# Companion_Board.net
KiCad netlist of a schematic drawn in EAGLE
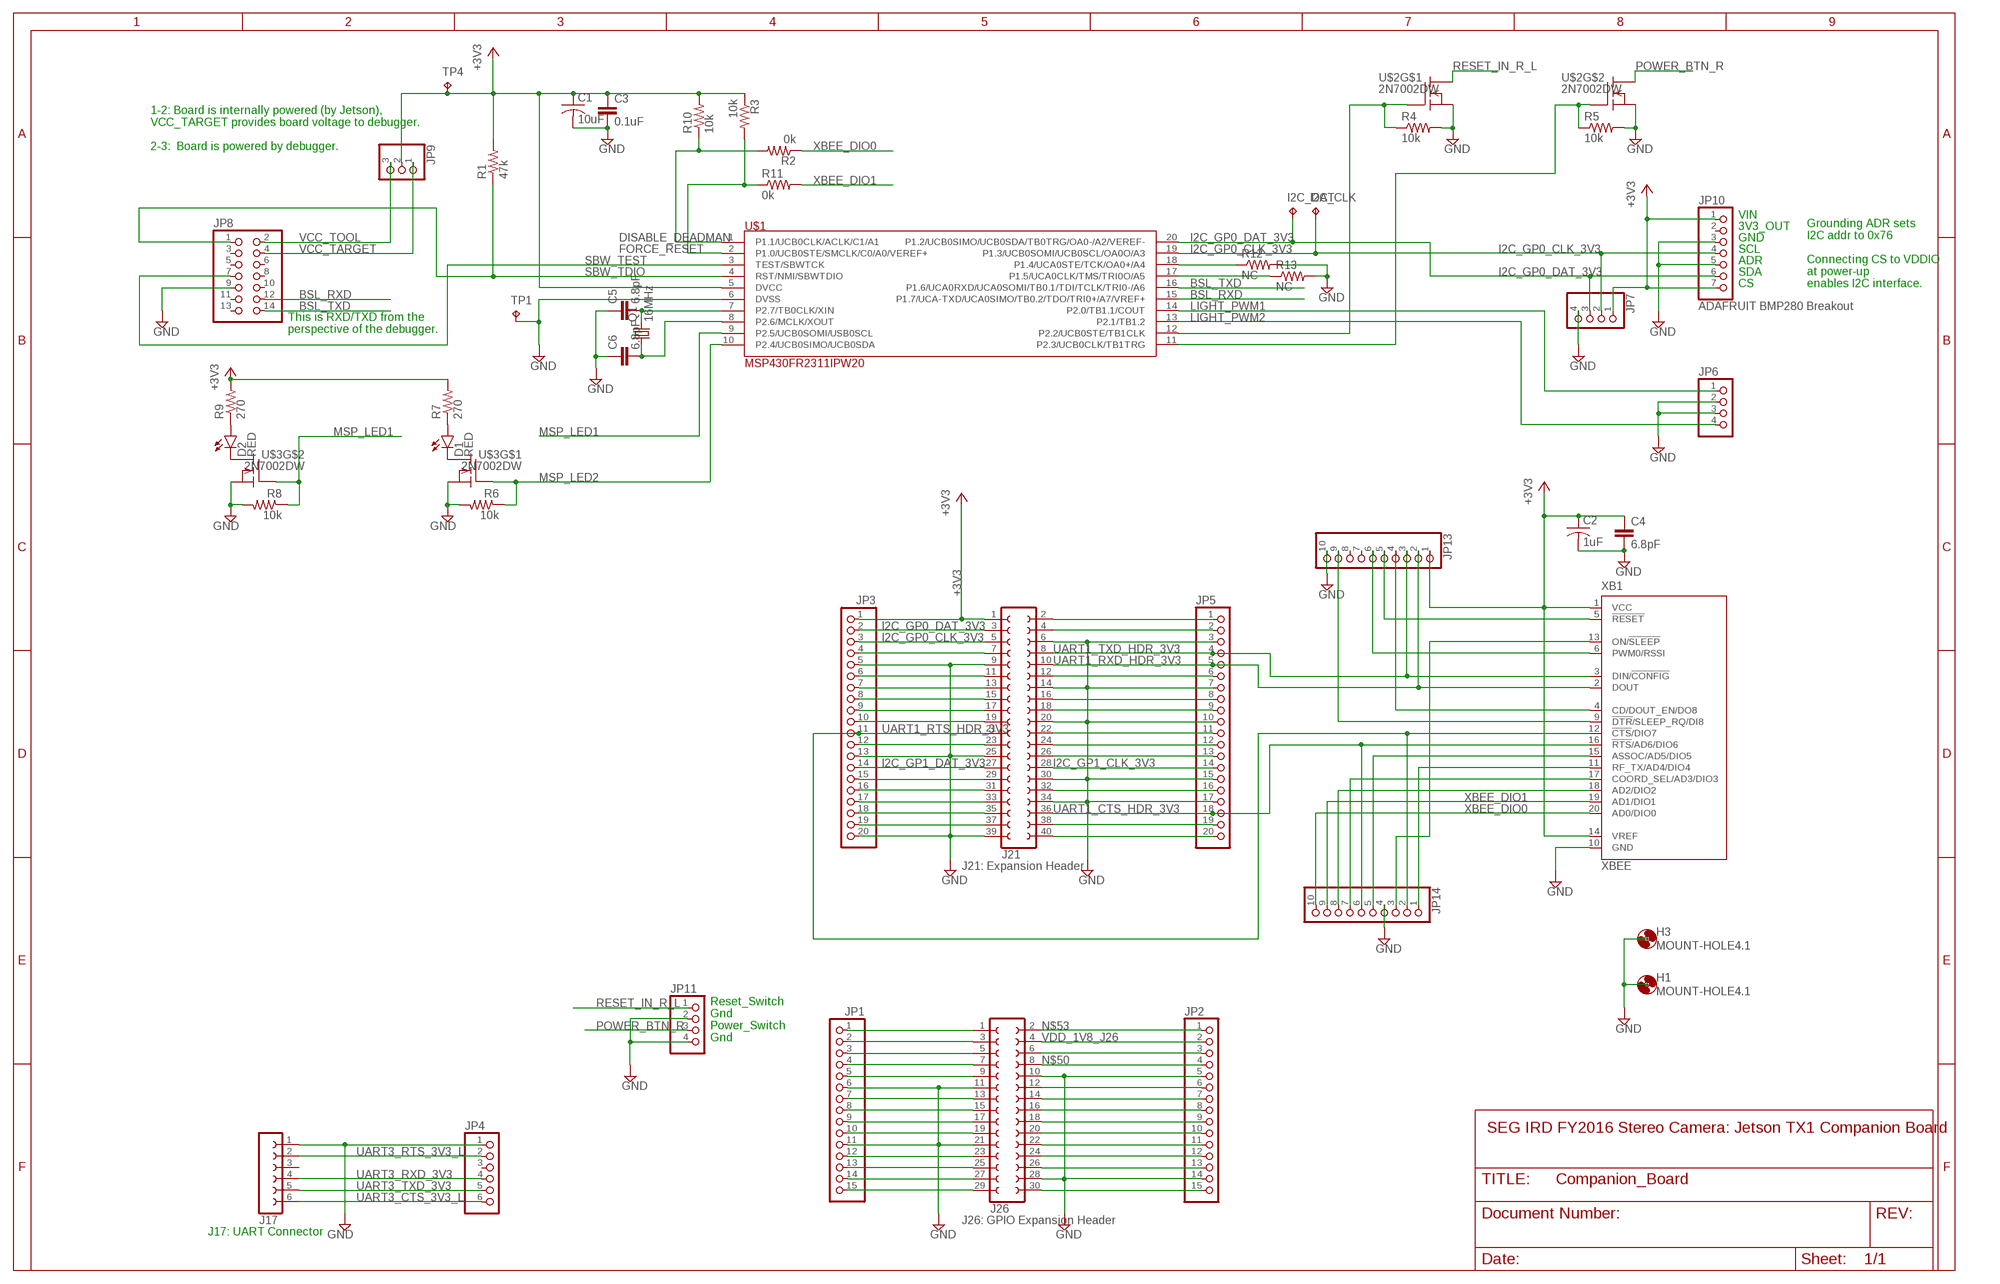
[diagram p0: schematic, sheet 1]

(export (version "E")
  (design (tool "Eeschema 10.0.6"))
  (components
    (comp (ref "C1")
      (value "10uF")
      (footprint "eagle-import:C1206")
      (libsource (lib "eagle-import") (part "C-USC1206"))
    )
    (comp (ref "C2")
      (value "1uF")
      (footprint "eagle-import:C1206")
      (libsource (lib "eagle-import") (part "C-USC1206"))
    )
    (comp (ref "C3")
      (value "0.1uF")
      (footprint "eagle-import:C0805")
      (libsource (lib "eagle-import") (part "C-EUC0805"))
    )
    (comp (ref "C4")
      (value "6.8pF")
      (footprint "eagle-import:C0805")
      (libsource (lib "eagle-import") (part "C-EUC0805"))
    )
    (comp (ref "C5")
      (value "6.8pF")
      (footprint "eagle-import:C0805")
      (libsource (lib "eagle-import") (part "C-EUC0805"))
    )
    (comp (ref "C6")
      (value "6.8pF")
      (footprint "eagle-import:C0805")
      (libsource (lib "eagle-import") (part "C-EUC0805"))
    )
    (comp (ref "D1")
      (value "RED")
      (footprint "eagle-import:LED-1206")
      (libsource (lib "eagle-import") (part "LED-RED1206"))
    )
    (comp (ref "D2")
      (value "RED")
      (footprint "eagle-import:LED-1206")
      (libsource (lib "eagle-import") (part "LED-RED1206"))
    )
    (comp (ref "H1")
      (value "MOUNT-HOLE4.1")
      (footprint "eagle-import:4,1")
      (libsource (lib "eagle-import") (part "MOUNT-HOLE4.1"))
    )
    (comp (ref "H3")
      (value "MOUNT-HOLE4.1")
      (footprint "eagle-import:4,1")
      (libsource (lib "eagle-import") (part "MOUNT-HOLE4.1"))
    )
    (comp (ref "I2C_CLK")
      (value "TPPAD1-13")
      (footprint "eagle-import:P1-13")
      (libsource (lib "eagle-import") (part "TPPAD1-13"))
    )
    (comp (ref "I2C_DAT")
      (value "TPPAD1-13")
      (footprint "eagle-import:P1-13")
      (libsource (lib "eagle-import") (part "TPPAD1-13"))
    )
    (comp (ref "J17")
      (value "FE06-1")
      (footprint "eagle-import:FE06")
      (libsource (lib "eagle-import") (part "FE06-1"))
    )
    (comp (ref "J21")
      (value "FE20-2")
      (footprint "eagle-import:FE20-2")
      (libsource (lib "eagle-import") (part "FE20-2"))
    )
    (comp (ref "J26")
      (value "FE15-2")
      (footprint "eagle-import:FE15-2")
      (libsource (lib "eagle-import") (part "FE15-2"))
    )
    (comp (ref "JP1")
      (value "PINHD-1X15")
      (footprint "eagle-import:1X15")
      (libsource (lib "eagle-import") (part "PINHD-1X15"))
    )
    (comp (ref "JP2")
      (value "PINHD-1X15")
      (footprint "eagle-import:1X15")
      (libsource (lib "eagle-import") (part "PINHD-1X15"))
    )
    (comp (ref "JP3")
      (value "PINHD-1X20")
      (footprint "eagle-import:1X20")
      (libsource (lib "eagle-import") (part "PINHD-1X20"))
    )
    (comp (ref "JP4")
      (value "PINHD-1X6")
      (footprint "eagle-import:1X06")
      (libsource (lib "eagle-import") (part "PINHD-1X6"))
    )
    (comp (ref "JP5")
      (value "PINHD-1X20")
      (footprint "eagle-import:1X20")
      (libsource (lib "eagle-import") (part "PINHD-1X20"))
    )
    (comp (ref "JP6")
      (value "PINHD-1X4/90")
      (footprint "eagle-import:1X04_90")
      (libsource (lib "eagle-import") (part "PINHD-1X4/90"))
    )
    (comp (ref "JP7")
      (value "PINHD-1X4")
      (footprint "eagle-import:1X04")
      (libsource (lib "eagle-import") (part "PINHD-1X4"))
    )
    (comp (ref "JP8")
      (value "PINHD-2X7")
      (footprint "eagle-import:2X07")
      (libsource (lib "eagle-import") (part "PINHD-2X7"))
    )
    (comp (ref "JP9")
      (value "PINHD-1X3")
      (footprint "eagle-import:1X03")
      (libsource (lib "eagle-import") (part "PINHD-1X3"))
    )
    (comp (ref "JP10")
      (value "ADAFRUIT BMP280 Breakout")
      (footprint "eagle-import:1X07")
      (libsource (lib "eagle-import") (part "ADAFRUIT_BMP280_BREAKOUT"))
    )
    (comp (ref "JP11")
      (value "PINHD-1X4/90")
      (footprint "eagle-import:1X04_90")
      (libsource (lib "eagle-import") (part "PINHD-1X4/90"))
    )
    (comp (ref "JP13")
      (value "PINHD-1X10")
      (footprint "eagle-import:1X10")
      (libsource (lib "eagle-import") (part "PINHD-1X10"))
    )
    (comp (ref "JP14")
      (value "PINHD-1X10")
      (footprint "eagle-import:1X10")
      (libsource (lib "eagle-import") (part "PINHD-1X10"))
    )
    (comp (ref "Q1")
      (value "16MHz")
      (footprint "eagle-import:HC49UP")
      (libsource (lib "eagle-import") (part "CRYSTALHC49UP"))
    )
    (comp (ref "R1")
      (value "47k")
      (footprint "eagle-import:R0805")
      (libsource (lib "eagle-import") (part "R-US_R0805"))
    )
    (comp (ref "R2")
      (value "0k")
      (footprint "eagle-import:R0805")
      (libsource (lib "eagle-import") (part "R-US_R0805"))
    )
    (comp (ref "R3")
      (value "10k")
      (footprint "eagle-import:R0805")
      (libsource (lib "eagle-import") (part "R-US_R0805"))
    )
    (comp (ref "R4")
      (value "10k")
      (footprint "eagle-import:R0805")
      (libsource (lib "eagle-import") (part "R-US_R0805"))
    )
    (comp (ref "R5")
      (value "10k")
      (footprint "eagle-import:R0805")
      (libsource (lib "eagle-import") (part "R-US_R0805"))
    )
    (comp (ref "R6")
      (value "10k")
      (footprint "eagle-import:R0805")
      (libsource (lib "eagle-import") (part "R-US_R0805"))
    )
    (comp (ref "R7")
      (value "270")
      (footprint "eagle-import:R0805")
      (libsource (lib "eagle-import") (part "R-US_R0805"))
    )
    (comp (ref "R8")
      (value "10k")
      (footprint "eagle-import:R0805")
      (libsource (lib "eagle-import") (part "R-US_R0805"))
    )
    (comp (ref "R9")
      (value "270")
      (footprint "eagle-import:R0805")
      (libsource (lib "eagle-import") (part "R-US_R0805"))
    )
    (comp (ref "R10")
      (value "10k")
      (footprint "eagle-import:R0805")
      (libsource (lib "eagle-import") (part "R-US_R0805"))
    )
    (comp (ref "R11")
      (value "0k")
      (footprint "eagle-import:R0805")
      (libsource (lib "eagle-import") (part "R-US_R0805"))
    )
    (comp (ref "R12")
      (value "NC")
      (footprint "eagle-import:R0805")
      (libsource (lib "eagle-import") (part "R-US_R0805"))
    )
    (comp (ref "R13")
      (value "NC")
      (footprint "eagle-import:R0805")
      (libsource (lib "eagle-import") (part "R-US_R0805"))
    )
    (comp (ref "TP1")
      (value "TPPAD1-13")
      (footprint "eagle-import:P1-13")
      (libsource (lib "eagle-import") (part "TPPAD1-13"))
    )
    (comp (ref "TP4")
      (value "TPPAD1-13")
      (footprint "eagle-import:P1-13")
      (libsource (lib "eagle-import") (part "TPPAD1-13"))
    )
    (comp (ref "U$1")
      (value "MSP430FR2311IPW20")
      (footprint "eagle-import:SOP65P640X120-20N")
      (libsource (lib "eagle-import") (part "MSP430FR2311IPW20"))
    )
    (comp (ref "U$2")
      (value "2N7002DW")
      (footprint "eagle-import:SOT363")
      (libsource (lib "eagle-import") (part "2N7002DW"))
    )
    (comp (ref "U$3")
      (value "2N7002DW")
      (footprint "eagle-import:SOT363")
      (libsource (lib "eagle-import") (part "2N7002DW"))
    )
    (comp (ref "XB1")
      (value "XBEE")
      (footprint "eagle-import:XBEE")
      (fields (field (name "MPN") "XBP24-Z7UIT-004"))
      (libsource (lib "eagle-import") (part "XBEE"))
    )
  )
  (nets
    (net (code "1") (name "+3V3") (class "Default")
      (node (ref "C1") (pin "1") (pinfunction "1_1") (pintype "passive"))
      (node (ref "C2") (pin "1") (pinfunction "1_1") (pintype "passive"))
      (node (ref "C3") (pin "1") (pinfunction "1_1") (pintype "passive"))
      (node (ref "C4") (pin "1") (pinfunction "1_1") (pintype "passive"))
      (node (ref "J21") (pin "1") (pinfunction "1_1") (pintype "passive"))
      (node (ref "JP10") (pin "1") (pinfunction "1_1") (pintype "passive"))
      (node (ref "JP10") (pin "7") (pinfunction "7_7") (pintype "passive"))
      (node (ref "JP13") (pin "1") (pinfunction "1_1") (pintype "passive"))
      (node (ref "JP3") (pin "1") (pinfunction "1_1") (pintype "passive"))
      (node (ref "JP7") (pin "1") (pinfunction "1_1") (pintype "passive"))
      (node (ref "JP9") (pin "2") (pinfunction "2_2") (pintype "passive"))
      (node (ref "R1") (pin "2") (pinfunction "2_2") (pintype "passive"))
      (node (ref "R10") (pin "2") (pinfunction "2_2") (pintype "passive"))
      (node (ref "R3") (pin "1") (pinfunction "1_1") (pintype "passive"))
      (node (ref "R7") (pin "2") (pinfunction "2_2") (pintype "passive"))
      (node (ref "R9") (pin "2") (pinfunction "2_2") (pintype "passive"))
      (node (ref "TP4") (pin "TP") (pinfunction "TP_TP") (pintype "input"))
      (node (ref "U$1") (pin "5") (pinfunction "DVCC_5") (pintype "bidirectional"))
      (node (ref "XB1") (pin "1") (pinfunction "VCC_1") (pintype "power_in"))
      (node (ref "XB1") (pin "14") (pinfunction "VREF_14") (pintype "input"))
    )
    (net (code "2") (name "/BSL_RXD") (class "Default")
      (node (ref "JP8") (pin "12") (pinfunction "12_12") (pintype "passive"))
      (node (ref "U$1") (pin "15") (pinfunction "P1.7/UCA-TXD/UCA0SIMO/TB0.2/TDO/TRI0+/A7/VREF+_15") (pintype "bidirectional"))
    )
    (net (code "3") (name "/BSL_TXD") (class "Default")
      (node (ref "JP8") (pin "14") (pinfunction "14_14") (pintype "passive"))
      (node (ref "U$1") (pin "16") (pinfunction "P1.6/UCA0RXD/UCA0SOMI/TB0.1/TDI/TCLK/TRI0-/A6_16") (pintype "bidirectional"))
    )
    (net (code "4") (name "/DISABLE_DEADMAN") (class "Default")
      (node (ref "R10") (pin "1") (pinfunction "1_1") (pintype "passive"))
      (node (ref "R2") (pin "2") (pinfunction "2_2") (pintype "passive"))
      (node (ref "U$1") (pin "1") (pinfunction "P1.1/UCB0CLK/ACLK/C1/A1_1") (pintype "bidirectional"))
    )
    (net (code "5") (name "/FORCE_RESET") (class "Default")
      (node (ref "R11") (pin "1") (pinfunction "1_1") (pintype "passive"))
      (node (ref "R3") (pin "2") (pinfunction "2_2") (pintype "passive"))
      (node (ref "U$1") (pin "2") (pinfunction "P1.0/UCB0STE/SMCLK/C0/A0/VEREF+_2") (pintype "bidirectional"))
    )
    (net (code "6") (name "/I2C_GP0_CLK_3V3") (class "Default")
      (node (ref "I2C_CLK") (pin "TP") (pinfunction "TP_TP") (pintype "input"))
      (node (ref "J21") (pin "5") (pinfunction "5_5") (pintype "passive"))
      (node (ref "JP10") (pin "4") (pinfunction "4_4") (pintype "passive"))
      (node (ref "JP3") (pin "3") (pinfunction "3_3") (pintype "passive"))
      (node (ref "JP7") (pin "2") (pinfunction "2_2") (pintype "passive"))
      (node (ref "U$1") (pin "19") (pinfunction "P1.3/UCB0SOMI/UCB0SCL/OA0O/A3_19") (pintype "bidirectional"))
    )
    (net (code "7") (name "/I2C_GP0_DAT_3V3") (class "Default")
      (node (ref "I2C_DAT") (pin "TP") (pinfunction "TP_TP") (pintype "input"))
      (node (ref "J21") (pin "3") (pinfunction "3_3") (pintype "passive"))
      (node (ref "JP10") (pin "6") (pinfunction "6_6") (pintype "passive"))
      (node (ref "JP3") (pin "2") (pinfunction "2_2") (pintype "passive"))
      (node (ref "JP7") (pin "3") (pinfunction "3_3") (pintype "passive"))
      (node (ref "U$1") (pin "20") (pinfunction "P1.2/UCB0SIMO/UCB0SDA/TB0TRG/OA0-/A2/VEREF-_20") (pintype "bidirectional"))
    )
    (net (code "8") (name "/I2C_GP1_CLK_3V3") (class "Default")
      (node (ref "J21") (pin "28") (pinfunction "28_28") (pintype "passive"))
      (node (ref "JP5") (pin "14") (pinfunction "14_14") (pintype "passive"))
    )
    (net (code "9") (name "/I2C_GP1_DAT_3V3") (class "Default")
      (node (ref "J21") (pin "27") (pinfunction "27_27") (pintype "passive"))
      (node (ref "JP3") (pin "14") (pinfunction "14_14") (pintype "passive"))
    )
    (net (code "10") (name "/LIGHT_PWM1") (class "Default")
      (node (ref "JP6") (pin "1") (pinfunction "1_1") (pintype "passive"))
      (node (ref "U$1") (pin "14") (pinfunction "P2.0/TB1.1/COUT_14") (pintype "bidirectional"))
    )
    (net (code "11") (name "/LIGHT_PWM2") (class "Default")
      (node (ref "JP6") (pin "4") (pinfunction "4_4") (pintype "passive"))
      (node (ref "U$1") (pin "13") (pinfunction "P2.1/TB1.2_13") (pintype "bidirectional"))
    )
    (net (code "12") (name "/MSP_LED1") (class "Default")
      (node (ref "R8") (pin "1") (pinfunction "1_1") (pintype "passive"))
      (node (ref "U$1") (pin "9") (pinfunction "P2.5/UCB0SOMI/USB0SCL_9") (pintype "bidirectional"))
      (node (ref "U$3") (pin "5") (pinfunction "G_5") (pintype "passive"))
    )
    (net (code "13") (name "/MSP_LED2") (class "Default")
      (node (ref "R6") (pin "1") (pinfunction "1_1") (pintype "passive"))
      (node (ref "U$1") (pin "10") (pinfunction "P2.4/UCB0SIMO/UCB0SDA_10") (pintype "bidirectional"))
      (node (ref "U$3") (pin "2") (pinfunction "G_2") (pintype "passive"))
    )
    (net (code "14") (name "/N$50") (class "Default")
      (node (ref "J21") (pin "4") (pinfunction "4_4") (pintype "passive"))
      (node (ref "JP5") (pin "2") (pinfunction "2_2") (pintype "passive"))
    )
    (net (code "15") (name "/N$53") (class "Default")
      (node (ref "J21") (pin "17") (pinfunction "17_17") (pintype "passive"))
      (node (ref "JP3") (pin "9") (pinfunction "9_9") (pintype "passive"))
    )
    (net (code "16") (name "/POWER_BTN_R") (class "Default")
      (node (ref "JP11") (pin "3") (pinfunction "3_3") (pintype "passive"))
      (node (ref "U$2") (pin "3") (pinfunction "D_3") (pintype "passive"))
    )
    (net (code "17") (name "/RESET_IN_R_L") (class "Default")
      (node (ref "JP11") (pin "1") (pinfunction "1_1") (pintype "passive"))
      (node (ref "U$2") (pin "6") (pinfunction "D_6") (pintype "passive"))
    )
    (net (code "18") (name "/SBW_TDIO") (class "Default")
      (node (ref "JP8") (pin "1") (pinfunction "1_1") (pintype "passive"))
      (node (ref "R1") (pin "1") (pinfunction "1_1") (pintype "passive"))
      (node (ref "U$1") (pin "4") (pinfunction "RST/NMI/SBWTDIO_4") (pintype "bidirectional"))
    )
    (net (code "19") (name "/SBW_TEST") (class "Default")
      (node (ref "JP8") (pin "7") (pinfunction "7_7") (pintype "passive"))
      (node (ref "U$1") (pin "3") (pinfunction "TEST/SBWTCK_3") (pintype "bidirectional"))
    )
    (net (code "20") (name "/UART1_CTS_HDR_3V3") (class "Default")
      (node (ref "J21") (pin "36") (pinfunction "36_36") (pintype "passive"))
      (node (ref "JP14") (pin "6") (pinfunction "6_6") (pintype "passive"))
      (node (ref "JP5") (pin "18") (pinfunction "18_18") (pintype "passive"))
      (node (ref "XB1") (pin "16") (pinfunction "~{RTS}/AD6/DIO6_16") (pintype "bidirectional"))
    )
    (net (code "21") (name "/UART1_RTS_HDR_3V3") (class "Default")
      (node (ref "J21") (pin "21") (pinfunction "21_21") (pintype "passive"))
      (node (ref "JP14") (pin "2") (pinfunction "2_2") (pintype "passive"))
      (node (ref "JP3") (pin "11") (pinfunction "11_11") (pintype "passive"))
      (node (ref "XB1") (pin "12") (pinfunction "~{CTS}/DIO7_12") (pintype "bidirectional"))
    )
    (net (code "22") (name "/UART1_RXD_HDR_3V3") (class "Default")
      (node (ref "J21") (pin "10") (pinfunction "10_10") (pintype "passive"))
      (node (ref "JP13") (pin "2") (pinfunction "2_2") (pintype "passive"))
      (node (ref "JP5") (pin "5") (pinfunction "5_5") (pintype "passive"))
      (node (ref "XB1") (pin "2") (pinfunction "DOUT_2") (pintype "output"))
    )
    (net (code "23") (name "/UART1_TXD_HDR_3V3") (class "Default")
      (node (ref "J21") (pin "8") (pinfunction "8_8") (pintype "passive"))
      (node (ref "JP13") (pin "3") (pinfunction "3_3") (pintype "passive"))
      (node (ref "JP5") (pin "4") (pinfunction "4_4") (pintype "passive"))
      (node (ref "XB1") (pin "3") (pinfunction "DIN/~{CONFIG}_3") (pintype "input"))
    )
    (net (code "24") (name "/UART3_CTS_3V3_L") (class "Default")
      (node (ref "J17") (pin "6") (pinfunction "6_6") (pintype "passive"))
      (node (ref "JP4") (pin "6") (pinfunction "6_6") (pintype "passive"))
    )
    (net (code "25") (name "/UART3_RTS_3V3_L") (class "Default")
      (node (ref "J17") (pin "2") (pinfunction "2_2") (pintype "passive"))
      (node (ref "JP4") (pin "2") (pinfunction "2_2") (pintype "passive"))
    )
    (net (code "26") (name "/UART3_RXD_3V3") (class "Default")
      (node (ref "J17") (pin "4") (pinfunction "4_4") (pintype "passive"))
      (node (ref "JP4") (pin "4") (pinfunction "4_4") (pintype "passive"))
    )
    (net (code "27") (name "/UART3_TXD_3V3") (class "Default")
      (node (ref "J17") (pin "5") (pinfunction "5_5") (pintype "passive"))
      (node (ref "JP4") (pin "5") (pinfunction "5_5") (pintype "passive"))
    )
    (net (code "28") (name "/VCC_TARGET") (class "Default")
      (node (ref "JP8") (pin "4") (pinfunction "4_4") (pintype "passive"))
      (node (ref "JP9") (pin "1") (pinfunction "1_1") (pintype "passive"))
    )
    (net (code "29") (name "/VCC_TOOL") (class "Default")
      (node (ref "JP8") (pin "2") (pinfunction "2_2") (pintype "passive"))
      (node (ref "JP9") (pin "3") (pinfunction "3_3") (pintype "passive"))
    )
    (net (code "30") (name "/VDD_1V8_J26") (class "Default")
      (node (ref "J26") (pin "4") (pinfunction "4_4") (pintype "passive"))
      (node (ref "JP2") (pin "2") (pinfunction "2_2") (pintype "passive"))
    )
    (net (code "31") (name "/XBEE_DIO0") (class "Default")
      (node (ref "JP14") (pin "10") (pinfunction "10_10") (pintype "passive"))
      (node (ref "R2") (pin "1") (pinfunction "1_1") (pintype "passive"))
      (node (ref "XB1") (pin "20") (pinfunction "AD0/DIO0_20") (pintype "bidirectional"))
    )
    (net (code "32") (name "/XBEE_DIO1") (class "Default")
      (node (ref "JP14") (pin "9") (pinfunction "9_9") (pintype "passive"))
      (node (ref "R11") (pin "2") (pinfunction "2_2") (pintype "passive"))
      (node (ref "XB1") (pin "19") (pinfunction "AD1/DIO1_19") (pintype "bidirectional"))
    )
    (net (code "33") (name "GND") (class "Default")
      (node (ref "C1") (pin "2") (pinfunction "2_2") (pintype "passive"))
      (node (ref "C2") (pin "2") (pinfunction "2_2") (pintype "passive"))
      (node (ref "C3") (pin "2") (pinfunction "2_2") (pintype "passive"))
      (node (ref "C4") (pin "2") (pinfunction "2_2") (pintype "passive"))
      (node (ref "C5") (pin "1") (pinfunction "1_1") (pintype "passive"))
      (node (ref "C6") (pin "1") (pinfunction "1_1") (pintype "passive"))
      (node (ref "J17") (pin "1") (pinfunction "1_1") (pintype "passive"))
      (node (ref "J21") (pin "14") (pinfunction "14_14") (pintype "passive"))
      (node (ref "J21") (pin "20") (pinfunction "20_20") (pintype "passive"))
      (node (ref "J21") (pin "25") (pinfunction "25_25") (pintype "passive"))
      (node (ref "J21") (pin "30") (pinfunction "30_30") (pintype "passive"))
      (node (ref "J21") (pin "34") (pinfunction "34_34") (pintype "passive"))
      (node (ref "J21") (pin "39") (pinfunction "39_39") (pintype "passive"))
      (node (ref "J21") (pin "6") (pinfunction "6_6") (pintype "passive"))
      (node (ref "J21") (pin "9") (pinfunction "9_9") (pintype "passive"))
      (node (ref "J26") (pin "10") (pinfunction "10_10") (pintype "passive"))
      (node (ref "J26") (pin "11") (pinfunction "11_11") (pintype "passive"))
      (node (ref "J26") (pin "21") (pinfunction "21_21") (pintype "passive"))
      (node (ref "J26") (pin "28") (pinfunction "28_28") (pintype "passive"))
      (node (ref "JP1") (pin "11") (pinfunction "11_11") (pintype "passive"))
      (node (ref "JP1") (pin "6") (pinfunction "6_6") (pintype "passive"))
      (node (ref "JP10") (pin "3") (pinfunction "3_3") (pintype "passive"))
      (node (ref "JP10") (pin "5") (pinfunction "5_5") (pintype "passive"))
      (node (ref "JP11") (pin "2") (pinfunction "2_2") (pintype "passive"))
      (node (ref "JP11") (pin "4") (pinfunction "4_4") (pintype "passive"))
      (node (ref "JP13") (pin "10") (pinfunction "10_10") (pintype "passive"))
      (node (ref "JP14") (pin "4") (pinfunction "4_4") (pintype "passive"))
      (node (ref "JP2") (pin "14") (pinfunction "14_14") (pintype "passive"))
      (node (ref "JP2") (pin "5") (pinfunction "5_5") (pintype "passive"))
      (node (ref "JP3") (pin "13") (pinfunction "13_13") (pintype "passive"))
      (node (ref "JP3") (pin "20") (pinfunction "20_20") (pintype "passive"))
      (node (ref "JP3") (pin "5") (pinfunction "5_5") (pintype "passive"))
      (node (ref "JP4") (pin "1") (pinfunction "1_1") (pintype "passive"))
      (node (ref "JP5") (pin "10") (pinfunction "10_10") (pintype "passive"))
      (node (ref "JP5") (pin "15") (pinfunction "15_15") (pintype "passive"))
      (node (ref "JP5") (pin "17") (pinfunction "17_17") (pintype "passive"))
      (node (ref "JP5") (pin "3") (pinfunction "3_3") (pintype "passive"))
      (node (ref "JP5") (pin "7") (pinfunction "7_7") (pintype "passive"))
      (node (ref "JP6") (pin "2") (pinfunction "2_2") (pintype "passive"))
      (node (ref "JP6") (pin "3") (pinfunction "3_3") (pintype "passive"))
      (node (ref "JP7") (pin "4") (pinfunction "4_4") (pintype "passive"))
      (node (ref "JP8") (pin "9") (pinfunction "9_9") (pintype "passive"))
      (node (ref "R12") (pin "2") (pinfunction "2_2") (pintype "passive"))
      (node (ref "R13") (pin "2") (pinfunction "2_2") (pintype "passive"))
      (node (ref "R4") (pin "2") (pinfunction "2_2") (pintype "passive"))
      (node (ref "R5") (pin "2") (pinfunction "2_2") (pintype "passive"))
      (node (ref "R6") (pin "2") (pinfunction "2_2") (pintype "passive"))
      (node (ref "R8") (pin "2") (pinfunction "2_2") (pintype "passive"))
      (node (ref "TP1") (pin "TP") (pinfunction "TP_TP") (pintype "input"))
      (node (ref "U$1") (pin "6") (pinfunction "DVSS_6") (pintype "bidirectional"))
      (node (ref "U$2") (pin "1") (pinfunction "S_1") (pintype "passive"))
      (node (ref "U$2") (pin "4") (pinfunction "S_4") (pintype "passive"))
      (node (ref "U$3") (pin "1") (pinfunction "S_1") (pintype "passive"))
      (node (ref "U$3") (pin "4") (pinfunction "S_4") (pintype "passive"))
      (node (ref "XB1") (pin "10") (pinfunction "GND_10") (pintype "power_in"))
    )
    (net (code "34") (name "Net-(D1-PadA)") (class "Default")
      (node (ref "D1") (pin "A") (pinfunction "A_A") (pintype "passive"))
      (node (ref "R7") (pin "1") (pinfunction "1_1") (pintype "passive"))
    )
    (net (code "35") (name "Net-(D2-PadA)") (class "Default")
      (node (ref "D2") (pin "A") (pinfunction "A_A") (pintype "passive"))
      (node (ref "R9") (pin "1") (pinfunction "1_1") (pintype "passive"))
    )
    (net (code "36") (name "Net-(J21-Pad2)") (class "Default")
      (node (ref "J21") (pin "2") (pinfunction "2_2") (pintype "passive"))
      (node (ref "JP5") (pin "1") (pinfunction "1_1") (pintype "passive"))
    )
    (net (code "37") (name "Net-(J21-Pad7)") (class "Default")
      (node (ref "J21") (pin "7") (pinfunction "7_7") (pintype "passive"))
      (node (ref "JP3") (pin "4") (pinfunction "4_4") (pintype "passive"))
    )
    (net (code "38") (name "Net-(J21-Pad11)") (class "Default")
      (node (ref "J21") (pin "11") (pinfunction "11_11") (pintype "passive"))
      (node (ref "JP3") (pin "6") (pinfunction "6_6") (pintype "passive"))
    )
    (net (code "39") (name "Net-(J21-Pad12)") (class "Default")
      (node (ref "J21") (pin "12") (pinfunction "12_12") (pintype "passive"))
      (node (ref "JP5") (pin "6") (pinfunction "6_6") (pintype "passive"))
    )
    (net (code "40") (name "Net-(J21-Pad13)") (class "Default")
      (node (ref "J21") (pin "13") (pinfunction "13_13") (pintype "passive"))
      (node (ref "JP3") (pin "7") (pinfunction "7_7") (pintype "passive"))
    )
    (net (code "41") (name "Net-(J21-Pad15)") (class "Default")
      (node (ref "J21") (pin "15") (pinfunction "15_15") (pintype "passive"))
      (node (ref "JP3") (pin "8") (pinfunction "8_8") (pintype "passive"))
    )
    (net (code "42") (name "Net-(J21-Pad16)") (class "Default")
      (node (ref "J21") (pin "16") (pinfunction "16_16") (pintype "passive"))
      (node (ref "JP5") (pin "8") (pinfunction "8_8") (pintype "passive"))
    )
    (net (code "43") (name "Net-(J21-Pad18)") (class "Default")
      (node (ref "J21") (pin "18") (pinfunction "18_18") (pintype "passive"))
      (node (ref "JP5") (pin "9") (pinfunction "9_9") (pintype "passive"))
    )
    (net (code "44") (name "Net-(J21-Pad19)") (class "Default")
      (node (ref "J21") (pin "19") (pinfunction "19_19") (pintype "passive"))
      (node (ref "JP3") (pin "10") (pinfunction "10_10") (pintype "passive"))
    )
    (net (code "45") (name "Net-(J21-Pad22)") (class "Default")
      (node (ref "J21") (pin "22") (pinfunction "22_22") (pintype "passive"))
      (node (ref "JP5") (pin "11") (pinfunction "11_11") (pintype "passive"))
    )
    (net (code "46") (name "Net-(J21-Pad23)") (class "Default")
      (node (ref "J21") (pin "23") (pinfunction "23_23") (pintype "passive"))
      (node (ref "JP3") (pin "12") (pinfunction "12_12") (pintype "passive"))
    )
    (net (code "47") (name "Net-(J21-Pad24)") (class "Default")
      (node (ref "J21") (pin "24") (pinfunction "24_24") (pintype "passive"))
      (node (ref "JP5") (pin "12") (pinfunction "12_12") (pintype "passive"))
    )
    (net (code "48") (name "Net-(J21-Pad26)") (class "Default")
      (node (ref "J21") (pin "26") (pinfunction "26_26") (pintype "passive"))
      (node (ref "JP5") (pin "13") (pinfunction "13_13") (pintype "passive"))
    )
    (net (code "49") (name "Net-(J21-Pad29)") (class "Default")
      (node (ref "J21") (pin "29") (pinfunction "29_29") (pintype "passive"))
      (node (ref "JP3") (pin "15") (pinfunction "15_15") (pintype "passive"))
    )
    (net (code "50") (name "Net-(J21-Pad31)") (class "Default")
      (node (ref "J21") (pin "31") (pinfunction "31_31") (pintype "passive"))
      (node (ref "JP3") (pin "16") (pinfunction "16_16") (pintype "passive"))
    )
    (net (code "51") (name "Net-(J21-Pad32)") (class "Default")
      (node (ref "J21") (pin "32") (pinfunction "32_32") (pintype "passive"))
      (node (ref "JP5") (pin "16") (pinfunction "16_16") (pintype "passive"))
    )
    (net (code "52") (name "Net-(J21-Pad33)") (class "Default")
      (node (ref "J21") (pin "33") (pinfunction "33_33") (pintype "passive"))
      (node (ref "JP3") (pin "17") (pinfunction "17_17") (pintype "passive"))
    )
    (net (code "53") (name "Net-(J21-Pad35)") (class "Default")
      (node (ref "J21") (pin "35") (pinfunction "35_35") (pintype "passive"))
      (node (ref "JP3") (pin "18") (pinfunction "18_18") (pintype "passive"))
    )
    (net (code "54") (name "Net-(J21-Pad37)") (class "Default")
      (node (ref "J21") (pin "37") (pinfunction "37_37") (pintype "passive"))
      (node (ref "JP3") (pin "19") (pinfunction "19_19") (pintype "passive"))
    )
    (net (code "55") (name "Net-(J21-Pad38)") (class "Default")
      (node (ref "J21") (pin "38") (pinfunction "38_38") (pintype "passive"))
      (node (ref "JP5") (pin "19") (pinfunction "19_19") (pintype "passive"))
    )
    (net (code "56") (name "Net-(J21-Pad40)") (class "Default")
      (node (ref "J21") (pin "40") (pinfunction "40_40") (pintype "passive"))
      (node (ref "JP5") (pin "20") (pinfunction "20_20") (pintype "passive"))
    )
    (net (code "57") (name "Net-(J26-Pad1)") (class "Default")
      (node (ref "J26") (pin "1") (pinfunction "1_1") (pintype "passive"))
      (node (ref "JP1") (pin "1") (pinfunction "1_1") (pintype "passive"))
    )
    (net (code "58") (name "Net-(J26-Pad2)") (class "Default")
      (node (ref "J26") (pin "2") (pinfunction "2_2") (pintype "passive"))
      (node (ref "JP2") (pin "1") (pinfunction "1_1") (pintype "passive"))
    )
    (net (code "59") (name "Net-(J26-Pad3)") (class "Default")
      (node (ref "J26") (pin "3") (pinfunction "3_3") (pintype "passive"))
      (node (ref "JP1") (pin "2") (pinfunction "2_2") (pintype "passive"))
    )
    (net (code "60") (name "Net-(J26-Pad5)") (class "Default")
      (node (ref "J26") (pin "5") (pinfunction "5_5") (pintype "passive"))
      (node (ref "JP1") (pin "3") (pinfunction "3_3") (pintype "passive"))
    )
    (net (code "61") (name "Net-(J26-Pad6)") (class "Default")
      (node (ref "J26") (pin "6") (pinfunction "6_6") (pintype "passive"))
      (node (ref "JP2") (pin "3") (pinfunction "3_3") (pintype "passive"))
    )
    (net (code "62") (name "Net-(J26-Pad7)") (class "Default")
      (node (ref "J26") (pin "7") (pinfunction "7_7") (pintype "passive"))
      (node (ref "JP1") (pin "4") (pinfunction "4_4") (pintype "passive"))
    )
    (net (code "63") (name "Net-(J26-Pad8)") (class "Default")
      (node (ref "J26") (pin "8") (pinfunction "8_8") (pintype "passive"))
      (node (ref "JP2") (pin "4") (pinfunction "4_4") (pintype "passive"))
    )
    (net (code "64") (name "Net-(J26-Pad9)") (class "Default")
      (node (ref "J26") (pin "9") (pinfunction "9_9") (pintype "passive"))
      (node (ref "JP1") (pin "5") (pinfunction "5_5") (pintype "passive"))
    )
    (net (code "65") (name "Net-(J26-Pad12)") (class "Default")
      (node (ref "J26") (pin "12") (pinfunction "12_12") (pintype "passive"))
      (node (ref "JP2") (pin "6") (pinfunction "6_6") (pintype "passive"))
    )
    (net (code "66") (name "Net-(J26-Pad13)") (class "Default")
      (node (ref "J26") (pin "13") (pinfunction "13_13") (pintype "passive"))
      (node (ref "JP1") (pin "7") (pinfunction "7_7") (pintype "passive"))
    )
    (net (code "67") (name "Net-(J26-Pad14)") (class "Default")
      (node (ref "J26") (pin "14") (pinfunction "14_14") (pintype "passive"))
      (node (ref "JP2") (pin "7") (pinfunction "7_7") (pintype "passive"))
    )
    (net (code "68") (name "Net-(J26-Pad15)") (class "Default")
      (node (ref "J26") (pin "15") (pinfunction "15_15") (pintype "passive"))
      (node (ref "JP1") (pin "8") (pinfunction "8_8") (pintype "passive"))
    )
    (net (code "69") (name "Net-(J26-Pad16)") (class "Default")
      (node (ref "J26") (pin "16") (pinfunction "16_16") (pintype "passive"))
      (node (ref "JP2") (pin "8") (pinfunction "8_8") (pintype "passive"))
    )
    (net (code "70") (name "Net-(J26-Pad17)") (class "Default")
      (node (ref "J26") (pin "17") (pinfunction "17_17") (pintype "passive"))
      (node (ref "JP1") (pin "9") (pinfunction "9_9") (pintype "passive"))
    )
    (net (code "71") (name "Net-(J26-Pad18)") (class "Default")
      (node (ref "J26") (pin "18") (pinfunction "18_18") (pintype "passive"))
      (node (ref "JP2") (pin "9") (pinfunction "9_9") (pintype "passive"))
    )
    (net (code "72") (name "Net-(J26-Pad19)") (class "Default")
      (node (ref "J26") (pin "19") (pinfunction "19_19") (pintype "passive"))
      (node (ref "JP1") (pin "10") (pinfunction "10_10") (pintype "passive"))
    )
    (net (code "73") (name "Net-(J26-Pad20)") (class "Default")
      (node (ref "J26") (pin "20") (pinfunction "20_20") (pintype "passive"))
      (node (ref "JP2") (pin "10") (pinfunction "10_10") (pintype "passive"))
    )
    (net (code "74") (name "Net-(J26-Pad22)") (class "Default")
      (node (ref "J26") (pin "22") (pinfunction "22_22") (pintype "passive"))
      (node (ref "JP2") (pin "11") (pinfunction "11_11") (pintype "passive"))
    )
    (net (code "75") (name "Net-(J26-Pad23)") (class "Default")
      (node (ref "J26") (pin "23") (pinfunction "23_23") (pintype "passive"))
      (node (ref "JP1") (pin "12") (pinfunction "12_12") (pintype "passive"))
    )
    (net (code "76") (name "Net-(J26-Pad24)") (class "Default")
      (node (ref "J26") (pin "24") (pinfunction "24_24") (pintype "passive"))
      (node (ref "JP2") (pin "12") (pinfunction "12_12") (pintype "passive"))
    )
    (net (code "77") (name "Net-(J26-Pad25)") (class "Default")
      (node (ref "J26") (pin "25") (pinfunction "25_25") (pintype "passive"))
      (node (ref "JP1") (pin "13") (pinfunction "13_13") (pintype "passive"))
    )
    (net (code "78") (name "Net-(J26-Pad26)") (class "Default")
      (node (ref "J26") (pin "26") (pinfunction "26_26") (pintype "passive"))
      (node (ref "JP2") (pin "13") (pinfunction "13_13") (pintype "passive"))
    )
    (net (code "79") (name "Net-(J26-Pad27)") (class "Default")
      (node (ref "J26") (pin "27") (pinfunction "27_27") (pintype "passive"))
      (node (ref "JP1") (pin "14") (pinfunction "14_14") (pintype "passive"))
    )
    (net (code "80") (name "Net-(J26-Pad29)") (class "Default")
      (node (ref "J26") (pin "29") (pinfunction "29_29") (pintype "passive"))
      (node (ref "JP1") (pin "15") (pinfunction "15_15") (pintype "passive"))
    )
    (net (code "81") (name "Net-(J26-Pad30)") (class "Default")
      (node (ref "J26") (pin "30") (pinfunction "30_30") (pintype "passive"))
      (node (ref "JP2") (pin "15") (pinfunction "15_15") (pintype "passive"))
    )
    (net (code "82") (name "Net-(U$1-P1.4{slash}UCA0STE{slash}TCK{slash}OA0+{slash}A4)") (class "Default")
      (node (ref "R12") (pin "1") (pinfunction "1_1") (pintype "passive"))
      (node (ref "U$1") (pin "18") (pinfunction "P1.4/UCA0STE/TCK/OA0+/A4_18") (pintype "bidirectional"))
    )
    (net (code "83") (name "Net-(U$1-P1.5{slash}UCA0CLK{slash}TMS{slash}TRI0O{slash}A5)") (class "Default")
      (node (ref "R13") (pin "1") (pinfunction "1_1") (pintype "passive"))
      (node (ref "U$1") (pin "17") (pinfunction "P1.5/UCA0CLK/TMS/TRI0O/A5_17") (pintype "bidirectional"))
    )
    (net (code "84") (name "Net-(U$1-P2.2{slash}UCB0STE{slash}TB1CLK)") (class "Default")
      (node (ref "R4") (pin "1") (pinfunction "1_1") (pintype "passive"))
      (node (ref "U$1") (pin "12") (pinfunction "P2.2/UCB0STE/TB1CLK_12") (pintype "bidirectional"))
      (node (ref "U$2") (pin "2") (pinfunction "G_2") (pintype "passive"))
    )
    (net (code "85") (name "Net-(U$1-P2.3{slash}UCB0CLK{slash}TB1TRG)") (class "Default")
      (node (ref "R5") (pin "1") (pinfunction "1_1") (pintype "passive"))
      (node (ref "U$1") (pin "11") (pinfunction "P2.3/UCB0CLK/TB1TRG_11") (pintype "bidirectional"))
      (node (ref "U$2") (pin "5") (pinfunction "G_5") (pintype "passive"))
    )
    (net (code "86") (name "Net-(U$1-P2.6{slash}MCLK{slash}XOUT)") (class "Default")
      (node (ref "C6") (pin "2") (pinfunction "2_2") (pintype "passive"))
      (node (ref "Q1") (pin "1") (pinfunction "1_1") (pintype "passive"))
      (node (ref "U$1") (pin "8") (pinfunction "P2.6/MCLK/XOUT_8") (pintype "bidirectional"))
    )
    (net (code "87") (name "Net-(U$1-P2.7{slash}TB0CLK{slash}XIN)") (class "Default")
      (node (ref "C5") (pin "2") (pinfunction "2_2") (pintype "passive"))
      (node (ref "Q1") (pin "2") (pinfunction "2_2") (pintype "passive"))
      (node (ref "U$1") (pin "7") (pinfunction "P2.7/TB0CLK/XIN_7") (pintype "bidirectional"))
    )
    (net (code "88") (name "Net-(U$3A-D)") (class "Default")
      (node (ref "D1") (pin "C") (pinfunction "C_C") (pintype "passive"))
      (node (ref "U$3") (pin "6") (pinfunction "D_6") (pintype "passive"))
    )
    (net (code "89") (name "Net-(U$3B-D)") (class "Default")
      (node (ref "D2") (pin "C") (pinfunction "C_C") (pintype "passive"))
      (node (ref "U$3") (pin "3") (pinfunction "D_3") (pintype "passive"))
    )
    (net (code "90") (name "Net-(XB1-AD2{slash}DIO2)") (class "Default")
      (node (ref "JP14") (pin "8") (pinfunction "8_8") (pintype "passive"))
      (node (ref "XB1") (pin "18") (pinfunction "AD2/DIO2_18") (pintype "bidirectional"))
    )
    (net (code "91") (name "Net-(XB1-ASSOC{slash}AD5{slash}DIO5)") (class "Default")
      (node (ref "JP14") (pin "5") (pinfunction "5_5") (pintype "passive"))
      (node (ref "XB1") (pin "15") (pinfunction "ASSOC/AD5/DIO5_15") (pintype "bidirectional"))
    )
    (net (code "92") (name "Net-(XB1-CD{slash}DOUT_EN{slash}DO8)") (class "Default")
      (node (ref "JP13") (pin "4") (pinfunction "4_4") (pintype "passive"))
      (node (ref "XB1") (pin "4") (pinfunction "CD/DOUT_EN/DO8_4") (pintype "output"))
    )
    (net (code "93") (name "Net-(XB1-COORD_SEL{slash}AD3{slash}DIO3)") (class "Default")
      (node (ref "JP14") (pin "7") (pinfunction "7_7") (pintype "passive"))
      (node (ref "XB1") (pin "17") (pinfunction "COORD_SEL/AD3/DIO3_17") (pintype "bidirectional"))
    )
    (net (code "94") (name "Net-(XB1-ON{slash}~{SLEEP})") (class "Default")
      (node (ref "JP14") (pin "3") (pinfunction "3_3") (pintype "passive"))
      (node (ref "XB1") (pin "13") (pinfunction "ON/~{SLEEP}_13") (pintype "output"))
    )
    (net (code "95") (name "Net-(XB1-PWM0{slash}RSSI)") (class "Default")
      (node (ref "JP13") (pin "6") (pinfunction "6_6") (pintype "passive"))
      (node (ref "XB1") (pin "6") (pinfunction "PWM0/RSSI_6") (pintype "output"))
    )
    (net (code "96") (name "Net-(XB1-RF_TX{slash}AD4{slash}DIO4)") (class "Default")
      (node (ref "JP14") (pin "1") (pinfunction "1_1") (pintype "passive"))
      (node (ref "XB1") (pin "11") (pinfunction "RF_TX/AD4/DIO4_11") (pintype "bidirectional"))
    )
    (net (code "97") (name "Net-(XB1-~{DTR}{slash}SLEEP_RQ{slash}DI8)") (class "Default")
      (node (ref "JP13") (pin "9") (pinfunction "9_9") (pintype "passive"))
      (node (ref "XB1") (pin "9") (pinfunction "~{DTR}/SLEEP_RQ/DI8_9") (pintype "bidirectional"))
    )
    (net (code "98") (name "Net-(XB1-~{RESET})") (class "Default")
      (node (ref "JP13") (pin "5") (pinfunction "5_5") (pintype "passive"))
      (node (ref "XB1") (pin "5") (pinfunction "~{RESET}_5") (pintype "input"))
    )
    (net (code "99") (name "unconnected-(J17-Pad3)") (class "Default")
      (node (ref "J17") (pin "3") (pinfunction "3_3") (pintype "passive"))
    )
    (net (code "100") (name "unconnected-(JP4-Pad3)") (class "Default")
      (node (ref "JP4") (pin "3") (pinfunction "3_3") (pintype "passive"))
    )
    (net (code "101") (name "unconnected-(JP8-Pad3)") (class "Default")
      (node (ref "JP8") (pin "3") (pinfunction "3_3") (pintype "passive"))
    )
    (net (code "102") (name "unconnected-(JP8-Pad5)") (class "Default")
      (node (ref "JP8") (pin "5") (pinfunction "5_5") (pintype "passive"))
    )
    (net (code "103") (name "unconnected-(JP8-Pad6)") (class "Default")
      (node (ref "JP8") (pin "6") (pinfunction "6_6") (pintype "passive"))
    )
    (net (code "104") (name "unconnected-(JP8-Pad8)") (class "Default")
      (node (ref "JP8") (pin "8") (pinfunction "8_8") (pintype "passive"))
    )
    (net (code "105") (name "unconnected-(JP8-Pad10)") (class "Default")
      (node (ref "JP8") (pin "10") (pinfunction "10_10") (pintype "passive"))
    )
    (net (code "106") (name "unconnected-(JP8-Pad11)") (class "Default")
      (node (ref "JP8") (pin "11") (pinfunction "11_11") (pintype "passive"))
    )
    (net (code "107") (name "unconnected-(JP8-Pad13)") (class "Default")
      (node (ref "JP8") (pin "13") (pinfunction "13_13") (pintype "passive"))
    )
    (net (code "108") (name "unconnected-(JP10-Pad2)") (class "Default")
      (node (ref "JP10") (pin "2") (pinfunction "2_2") (pintype "passive"))
    )
    (net (code "109") (name "unconnected-(JP13-Pad7)") (class "Default")
      (node (ref "JP13") (pin "7") (pinfunction "7_7") (pintype "passive"))
    )
    (net (code "110") (name "unconnected-(JP13-Pad8)") (class "Default")
      (node (ref "JP13") (pin "8") (pinfunction "8_8") (pintype "passive"))
    )
  )
)
